# exciting_voltage.net
KiCad netlist of a schematic drawn in EAGLE
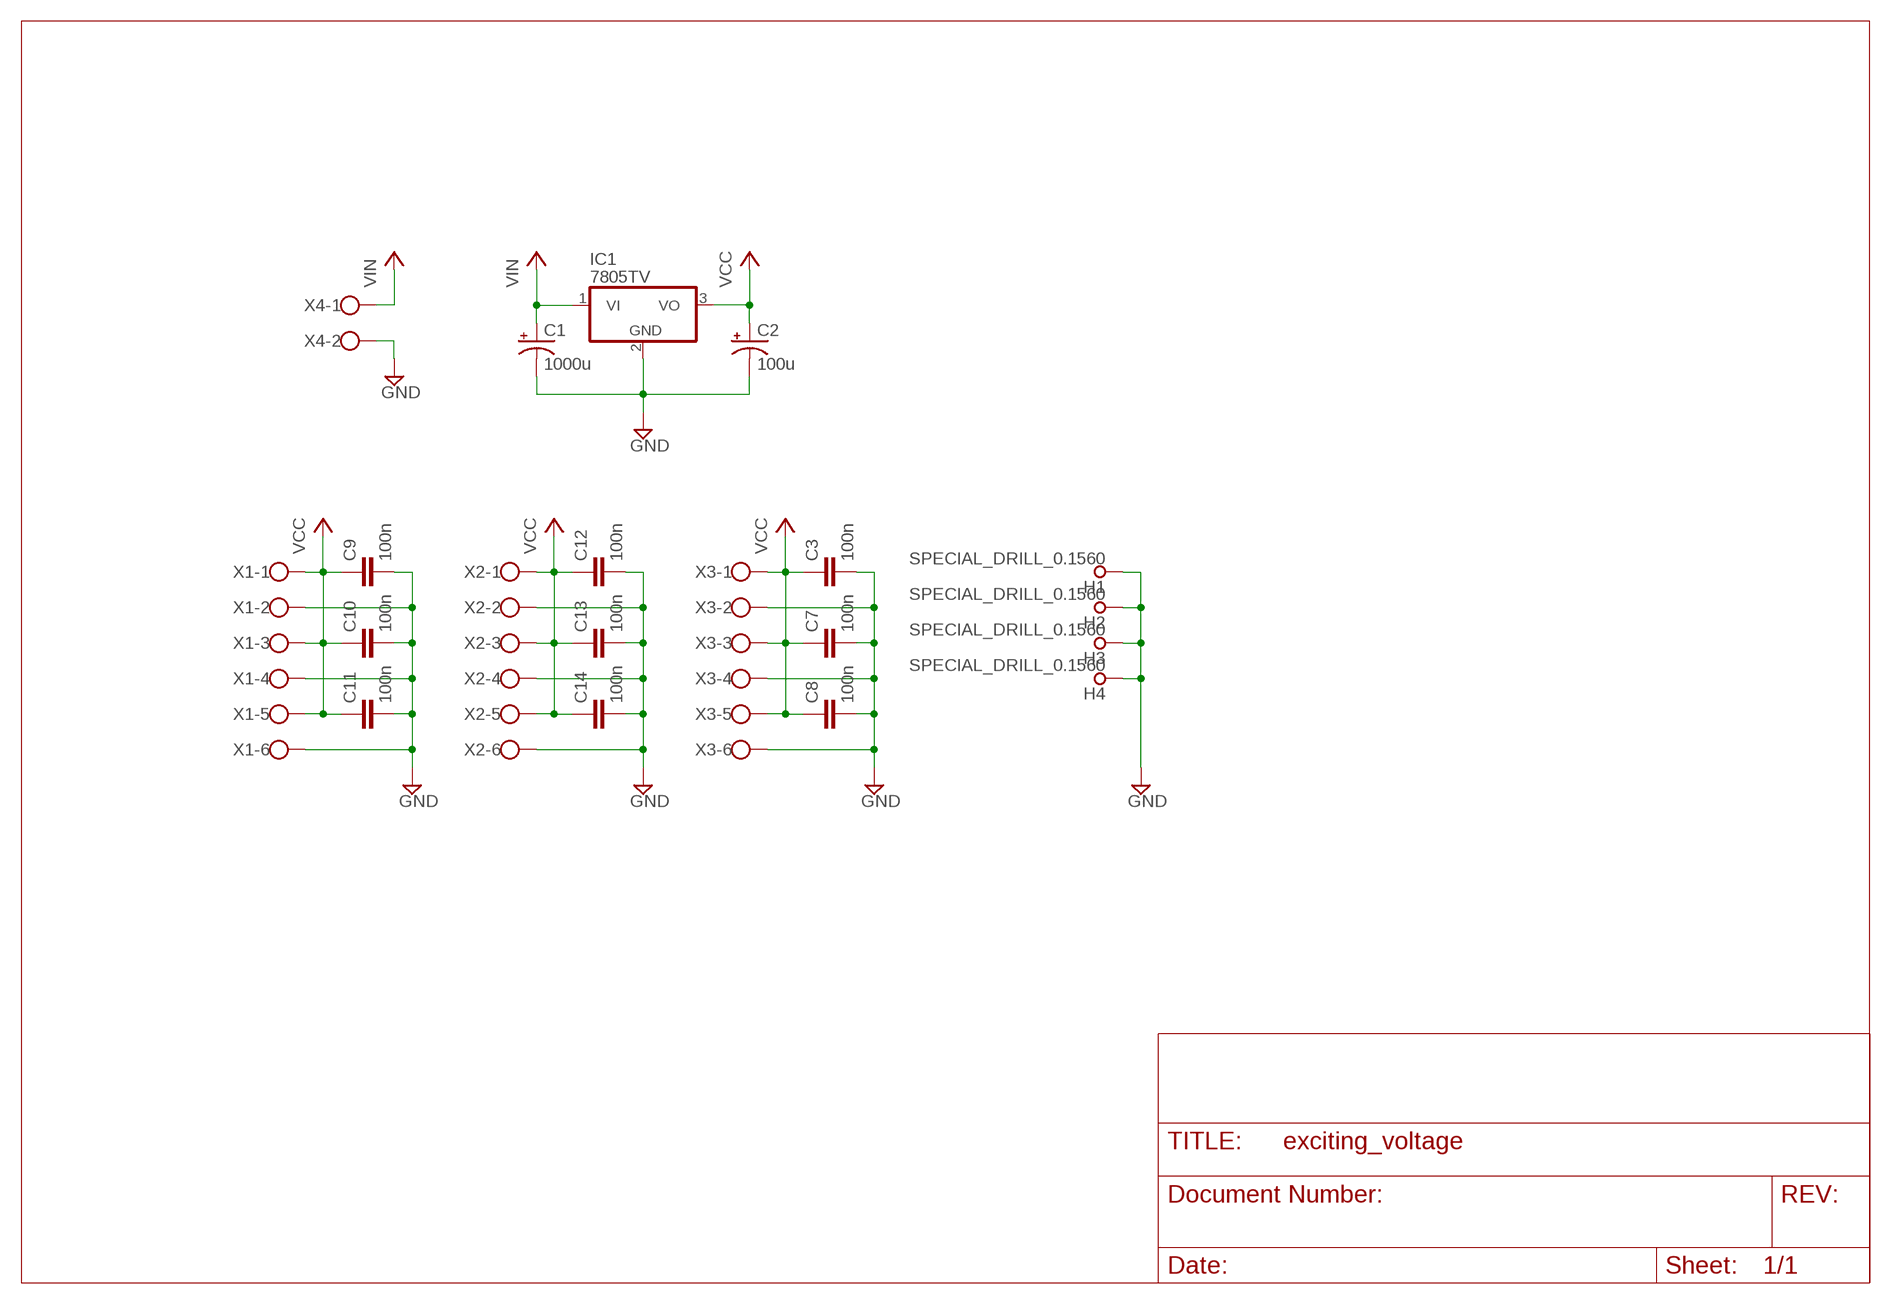
[diagram p0: schematic, sheet 1]

(export (version "E")
  (design (tool "Eeschema 10.0.6"))
  (components
    (comp (ref "C1")
      (value "1000u")
      (footprint "eagle-import:RCL_E5-13")
      (libsource (lib "eagle-import") (part "RCL_CPOL-USE5-13"))
    )
    (comp (ref "C2")
      (value "100u")
      (footprint "eagle-import:RCL_E2,5-7")
      (libsource (lib "eagle-import") (part "RCL_CPOL-USE2.5-7"))
    )
    (comp (ref "C3")
      (value "100n")
      (footprint "eagle-import:RCL_C050-025X075")
      (libsource (lib "eagle-import") (part "RCL_C-EU050-025X075"))
    )
    (comp (ref "C7")
      (value "100n")
      (footprint "eagle-import:RCL_C050-025X075")
      (libsource (lib "eagle-import") (part "RCL_C-EU050-025X075"))
    )
    (comp (ref "C8")
      (value "100n")
      (footprint "eagle-import:RCL_C050-025X075")
      (libsource (lib "eagle-import") (part "RCL_C-EU050-025X075"))
    )
    (comp (ref "C9")
      (value "100n")
      (footprint "eagle-import:RCL_C050-025X075")
      (libsource (lib "eagle-import") (part "RCL_C-EU050-025X075"))
    )
    (comp (ref "C10")
      (value "100n")
      (footprint "eagle-import:RCL_C050-025X075")
      (libsource (lib "eagle-import") (part "RCL_C-EU050-025X075"))
    )
    (comp (ref "C11")
      (value "100n")
      (footprint "eagle-import:RCL_C050-025X075")
      (libsource (lib "eagle-import") (part "RCL_C-EU050-025X075"))
    )
    (comp (ref "C12")
      (value "100n")
      (footprint "eagle-import:RCL_C050-025X075")
      (libsource (lib "eagle-import") (part "RCL_C-EU050-025X075"))
    )
    (comp (ref "C13")
      (value "100n")
      (footprint "eagle-import:RCL_C050-025X075")
      (libsource (lib "eagle-import") (part "RCL_C-EU050-025X075"))
    )
    (comp (ref "C14")
      (value "100n")
      (footprint "eagle-import:RCL_C050-025X075")
      (libsource (lib "eagle-import") (part "RCL_C-EU050-025X075"))
    )
    (comp (ref "H1")
      (value "SPECIAL_DRILL_0.1560")
      (footprint "eagle-import:PAD_0.1560")
      (libsource (lib "eagle-import") (part "SPECIAL_DRILL_0.1560"))
    )
    (comp (ref "H2")
      (value "SPECIAL_DRILL_0.1560")
      (footprint "eagle-import:PAD_0.1560")
      (libsource (lib "eagle-import") (part "SPECIAL_DRILL_0.1560"))
    )
    (comp (ref "H3")
      (value "SPECIAL_DRILL_0.1560")
      (footprint "eagle-import:PAD_0.1560")
      (libsource (lib "eagle-import") (part "SPECIAL_DRILL_0.1560"))
    )
    (comp (ref "H4")
      (value "SPECIAL_DRILL_0.1560")
      (footprint "eagle-import:PAD_0.1560")
      (libsource (lib "eagle-import") (part "SPECIAL_DRILL_0.1560"))
    )
    (comp (ref "IC1")
      (value "7805TV")
      (footprint "eagle-import:TO220V")
      (libsource (lib "eagle-import") (part "78TV05"))
    )
    (comp (ref "X1")
      (value "5EHDRC-6P")
      (footprint "eagle-import:5EHDRC-6P")
      (libsource (lib "eagle-import") (part "5EHDRC-6P"))
    )
    (comp (ref "X2")
      (value "5EHDRC-6P")
      (footprint "eagle-import:5EHDRC-6P")
      (libsource (lib "eagle-import") (part "5EHDRC-6P"))
    )
    (comp (ref "X3")
      (value "5EHDRC-6P")
      (footprint "eagle-import:5EHDRC-6P")
      (libsource (lib "eagle-import") (part "5EHDRC-6P"))
    )
    (comp (ref "X4")
      (value "5EHDRC-2P")
      (footprint "eagle-import:5EHDRC-2P")
      (libsource (lib "eagle-import") (part "5EHDRC-2P"))
    )
  )
  (nets
    (net (code "1") (name "GND") (class "Default")
      (node (ref "C1") (pin "-") (pinfunction "-_-") (pintype "passive"))
      (node (ref "C10") (pin "2") (pinfunction "2_2") (pintype "passive"))
      (node (ref "C11") (pin "2") (pinfunction "2_2") (pintype "passive"))
      (node (ref "C12") (pin "2") (pinfunction "2_2") (pintype "passive"))
      (node (ref "C13") (pin "2") (pinfunction "2_2") (pintype "passive"))
      (node (ref "C14") (pin "2") (pinfunction "2_2") (pintype "passive"))
      (node (ref "C2") (pin "-") (pinfunction "-_-") (pintype "passive"))
      (node (ref "C3") (pin "2") (pinfunction "2_2") (pintype "passive"))
      (node (ref "C7") (pin "2") (pinfunction "2_2") (pintype "passive"))
      (node (ref "C8") (pin "2") (pinfunction "2_2") (pintype "passive"))
      (node (ref "C9") (pin "2") (pinfunction "2_2") (pintype "passive"))
      (node (ref "H1") (pin "1") (pinfunction "1_1") (pintype "passive"))
      (node (ref "H2") (pin "1") (pinfunction "1_1") (pintype "passive"))
      (node (ref "H3") (pin "1") (pinfunction "1_1") (pintype "passive"))
      (node (ref "H4") (pin "1") (pinfunction "1_1") (pintype "passive"))
      (node (ref "IC1") (pin "2") (pinfunction "GND_2") (pintype "passive"))
      (node (ref "X1") (pin "2") (pinfunction "KL_2") (pintype "passive"))
      (node (ref "X1") (pin "4") (pinfunction "KL_4") (pintype "passive"))
      (node (ref "X1") (pin "6") (pinfunction "KL_6") (pintype "passive"))
      (node (ref "X2") (pin "2") (pinfunction "KL_2") (pintype "passive"))
      (node (ref "X2") (pin "4") (pinfunction "KL_4") (pintype "passive"))
      (node (ref "X2") (pin "6") (pinfunction "KL_6") (pintype "passive"))
      (node (ref "X3") (pin "2") (pinfunction "KL_2") (pintype "passive"))
      (node (ref "X3") (pin "4") (pinfunction "KL_4") (pintype "passive"))
      (node (ref "X3") (pin "6") (pinfunction "KL_6") (pintype "passive"))
      (node (ref "X4") (pin "2") (pinfunction "KL_2") (pintype "passive"))
    )
    (net (code "2") (name "VCC") (class "Default")
      (node (ref "C10") (pin "1") (pinfunction "1_1") (pintype "passive"))
      (node (ref "C11") (pin "1") (pinfunction "1_1") (pintype "passive"))
      (node (ref "C12") (pin "1") (pinfunction "1_1") (pintype "passive"))
      (node (ref "C13") (pin "1") (pinfunction "1_1") (pintype "passive"))
      (node (ref "C14") (pin "1") (pinfunction "1_1") (pintype "passive"))
      (node (ref "C2") (pin "+") (pinfunction "+_+") (pintype "passive"))
      (node (ref "C3") (pin "1") (pinfunction "1_1") (pintype "passive"))
      (node (ref "C7") (pin "1") (pinfunction "1_1") (pintype "passive"))
      (node (ref "C8") (pin "1") (pinfunction "1_1") (pintype "passive"))
      (node (ref "C9") (pin "1") (pinfunction "1_1") (pintype "passive"))
      (node (ref "IC1") (pin "3") (pinfunction "VO_3") (pintype "passive"))
      (node (ref "X1") (pin "1") (pinfunction "KL_1") (pintype "passive"))
      (node (ref "X1") (pin "3") (pinfunction "KL_3") (pintype "passive"))
      (node (ref "X1") (pin "5") (pinfunction "KL_5") (pintype "passive"))
      (node (ref "X2") (pin "1") (pinfunction "KL_1") (pintype "passive"))
      (node (ref "X2") (pin "3") (pinfunction "KL_3") (pintype "passive"))
      (node (ref "X2") (pin "5") (pinfunction "KL_5") (pintype "passive"))
      (node (ref "X3") (pin "1") (pinfunction "KL_1") (pintype "passive"))
      (node (ref "X3") (pin "3") (pinfunction "KL_3") (pintype "passive"))
      (node (ref "X3") (pin "5") (pinfunction "KL_5") (pintype "passive"))
    )
    (net (code "3") (name "VIN") (class "Default")
      (node (ref "C1") (pin "+") (pinfunction "+_+") (pintype "passive"))
      (node (ref "IC1") (pin "1") (pinfunction "VI_1") (pintype "input"))
      (node (ref "X4") (pin "1") (pinfunction "KL_1") (pintype "passive"))
    )
  )
)
